# PDB_Board.net
KiCad netlist of a schematic drawn in EAGLE
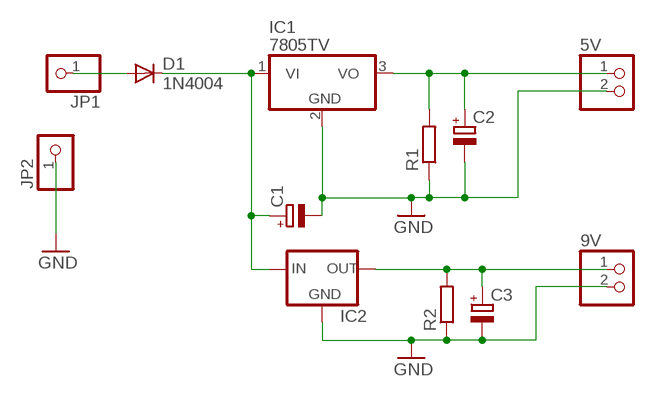
[diagram p0: schematic, sheet 1]

(export (version "E")
  (design (tool "Eeschema 10.0.6"))
  (components
    (comp (ref "5V")
      (value "PINHD-1X2/OCT")
      (footprint "eagle-import:1X02_OCT")
      (libsource (lib "eagle-import") (part "PINHD-1X2/OCT"))
    )
    (comp (ref "9V")
      (value "PINHD-1X2/OCT")
      (footprint "eagle-import:1X02_OCT")
      (libsource (lib "eagle-import") (part "PINHD-1X2/OCT"))
    )
    (comp (ref "C1")
      (value "CPOL-EUE3.5-8")
      (footprint "eagle-import:E3,5-8")
      (libsource (lib "eagle-import") (part "CPOL-EUE3.5-8"))
    )
    (comp (ref "C2")
      (value "CPOL-EUE2.5-5")
      (footprint "eagle-import:E2,5-5")
      (libsource (lib "eagle-import") (part "CPOL-EUE2.5-5"))
    )
    (comp (ref "C3")
      (value "CPOL-EUE2.5-5")
      (footprint "eagle-import:E2,5-5")
      (libsource (lib "eagle-import") (part "CPOL-EUE2.5-5"))
    )
    (comp (ref "D1")
      (value "1N4004")
      (footprint "eagle-import:DO41-10")
      (libsource (lib "eagle-import") (part "1N4004"))
    )
    (comp (ref "IC1")
      (value "7805TV")
      (footprint "eagle-import:TO220V")
      (libsource (lib "eagle-import") (part "78TV05"))
    )
    (comp (ref "IC2")
      (value "78XXS")
      (footprint "eagle-import:78XXS")
      (libsource (lib "eagle-import") (part "78XXS"))
    )
    (comp (ref "JP1")
      (value "PINHD-1X1")
      (footprint "eagle-import:1X01")
      (libsource (lib "eagle-import") (part "PINHD-1X1"))
    )
    (comp (ref "JP2")
      (value "PINHD-1X1")
      (footprint "eagle-import:1X01")
      (libsource (lib "eagle-import") (part "PINHD-1X1"))
    )
    (comp (ref "R1")
      (value "R-EU_0207/10")
      (footprint "eagle-import:0207_10")
      (libsource (lib "eagle-import") (part "R-EU_0207/10"))
    )
    (comp (ref "R2")
      (value "R-EU_0207/10")
      (footprint "eagle-import:0207_10")
      (libsource (lib "eagle-import") (part "R-EU_0207/10"))
    )
  )
  (nets
    (net (code "1") (name "GND") (class "Default")
      (node (ref "5V") (pin "2") (pinfunction "2_2") (pintype "passive"))
      (node (ref "9V") (pin "2") (pinfunction "2_2") (pintype "passive"))
      (node (ref "C1") (pin "-") (pinfunction "-_-") (pintype "passive"))
      (node (ref "C2") (pin "-") (pinfunction "-_-") (pintype "passive"))
      (node (ref "C3") (pin "-") (pinfunction "-_-") (pintype "passive"))
      (node (ref "IC1") (pin "2") (pinfunction "GND_2") (pintype "passive"))
      (node (ref "IC2") (pin "GND") (pinfunction "GND_GND") (pintype "input"))
      (node (ref "JP2") (pin "1") (pinfunction "1_1") (pintype "passive"))
      (node (ref "R1") (pin "1") (pinfunction "1_1") (pintype "passive"))
      (node (ref "R2") (pin "1") (pinfunction "1_1") (pintype "passive"))
    )
    (net (code "2") (name "Net-(9V-Pad1)") (class "Default")
      (node (ref "9V") (pin "1") (pinfunction "1_1") (pintype "passive"))
      (node (ref "C3") (pin "+") (pinfunction "+_+") (pintype "passive"))
      (node (ref "IC2") (pin "OUT") (pinfunction "OUT_OUT") (pintype "passive"))
      (node (ref "R2") (pin "2") (pinfunction "2_2") (pintype "passive"))
    )
    (net (code "3") (name "Net-(D1-PadA)") (class "Default")
      (node (ref "D1") (pin "A") (pinfunction "A_A") (pintype "passive"))
      (node (ref "JP1") (pin "1") (pinfunction "1_1") (pintype "passive"))
    )
    (net (code "4") (name "Net-(IC1-VI)") (class "Default")
      (node (ref "C1") (pin "+") (pinfunction "+_+") (pintype "passive"))
      (node (ref "D1") (pin "C") (pinfunction "C_C") (pintype "passive"))
      (node (ref "IC1") (pin "1") (pinfunction "VI_1") (pintype "input"))
      (node (ref "IC2") (pin "IN") (pinfunction "IN_IN") (pintype "input"))
    )
    (net (code "5") (name "Net-(IC1-VO)") (class "Default")
      (node (ref "5V") (pin "1") (pinfunction "1_1") (pintype "passive"))
      (node (ref "C2") (pin "+") (pinfunction "+_+") (pintype "passive"))
      (node (ref "IC1") (pin "3") (pinfunction "VO_3") (pintype "passive"))
      (node (ref "R1") (pin "2") (pinfunction "2_2") (pintype "passive"))
    )
  )
)
